# CH32M030C8U3-R0.net
KiCad netlist of a schematic drawn in Altium Designer
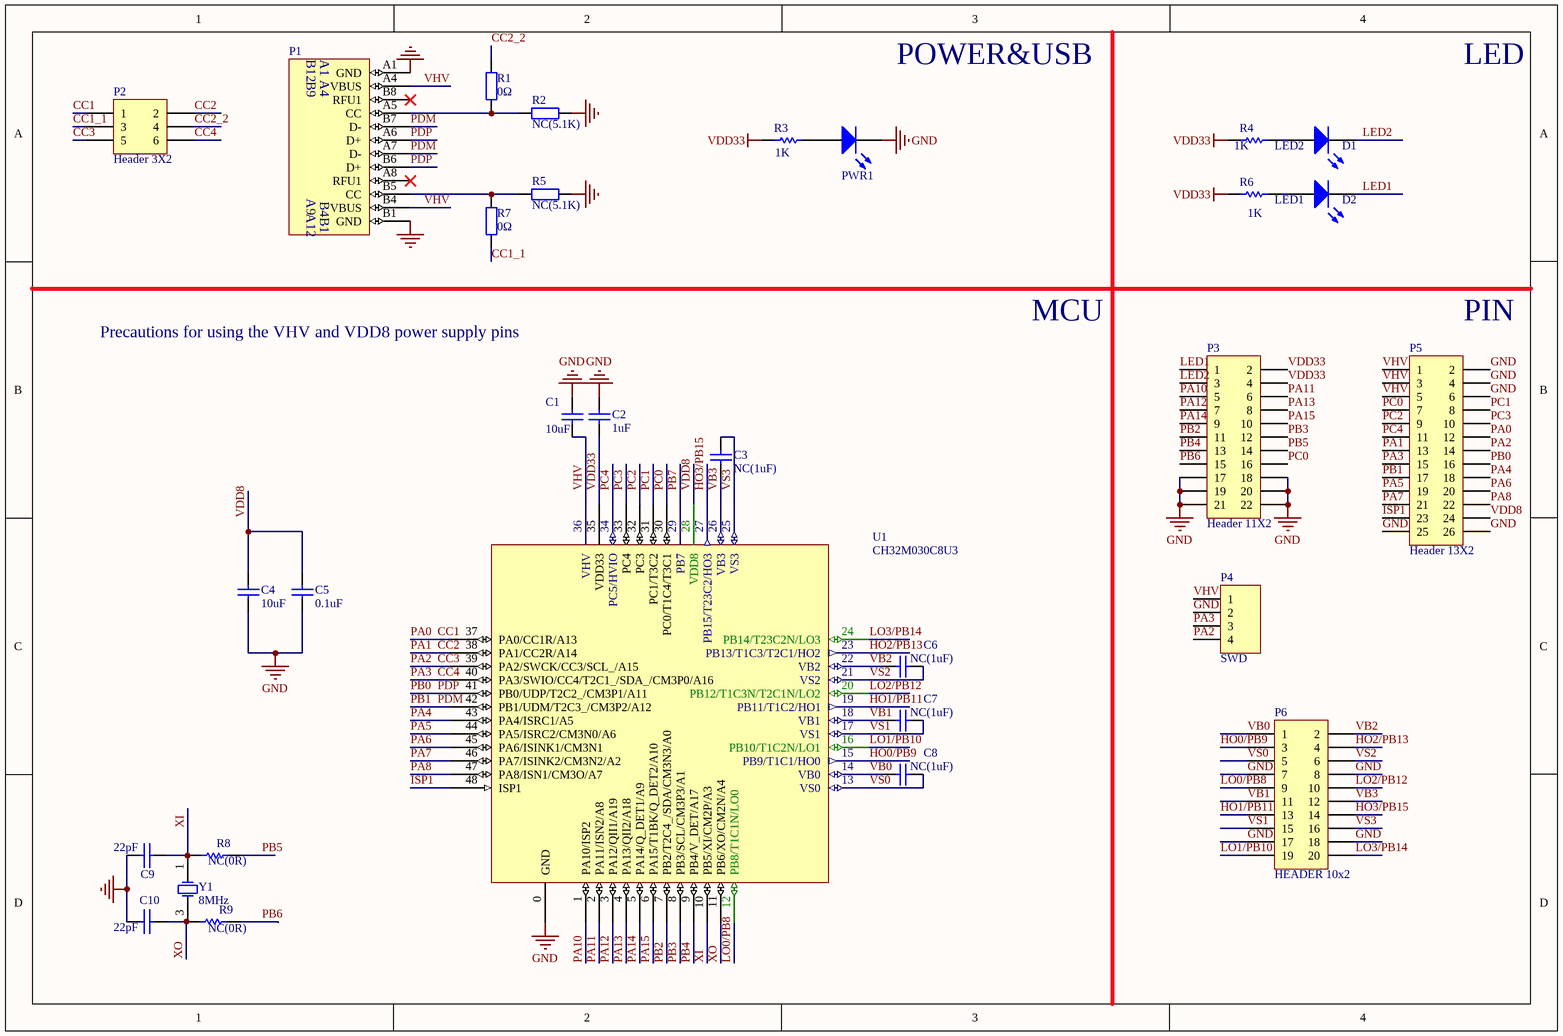
[diagram p0: CH32M030C8U3-R0.SchDoc]

(export (version "E")
  (design (tool "Eeschema 10.0.6"))
  (components
    (comp (ref "C1")
      (value "10uF")
      (footprint "0603_C")
      (description "Capacitor")
      (fields (field (name "PUBLISHER") "Altium Limited"))
      (libsource (lib "*") (part "Cap"))
    )
    (comp (ref "C2")
      (value "1uF")
      (footprint "0603_C")
      (description "Capacitor")
      (fields (field (name "PUBLISHER") "Altium Limited"))
      (libsource (lib "*") (part "Cap"))
    )
    (comp (ref "C3")
      (value "NC(1uF)")
      (footprint "0603_C")
      (description "Capacitor")
      (fields (field (name "PUBLISHER") "Altium Limited"))
      (libsource (lib "*") (part "Cap"))
    )
    (comp (ref "C4")
      (value "10uF")
      (footprint "0603_C")
      (description "Capacitor")
      (fields (field (name "PUBLISHER") "Altium Limited"))
      (libsource (lib "*") (part "Cap"))
    )
    (comp (ref "C5")
      (value "0.1uF")
      (footprint "0603_C")
      (description "Capacitor")
      (fields (field (name "PUBLISHER") "Altium Limited"))
      (libsource (lib "*") (part "Cap"))
    )
    (comp (ref "C6")
      (value "NC(1uF)")
      (footprint "0603_C")
      (description "Capacitor")
      (fields (field (name "PUBLISHER") "Altium Limited"))
      (libsource (lib "*") (part "Cap"))
    )
    (comp (ref "C7")
      (value "NC(1uF)")
      (footprint "0603_C")
      (description "Capacitor")
      (fields (field (name "PUBLISHER") "Altium Limited"))
      (libsource (lib "*") (part "Cap"))
    )
    (comp (ref "C8")
      (value "NC(1uF)")
      (footprint "0603_C")
      (description "Capacitor")
      (fields (field (name "PUBLISHER") "Altium Limited"))
      (libsource (lib "*") (part "Cap"))
    )
    (comp (ref "C9")
      (value "22pF")
      (footprint "0603_C")
      (description "Capacitor")
      (libsource (lib "*") (part "CAP"))
    )
    (comp (ref "C10")
      (value "22pF")
      (footprint "0603_C")
      (description "Capacitor")
      (libsource (lib "*") (part "CAP"))
    )
    (comp (ref "D1")
      (value "LED2")
      (footprint "0603+")
      (description "Typical INFRARED GaAs LED")
      (fields (field (name "PUBLISHER") "Altium Limited"))
      (libsource (lib "*") (part "LED0"))
    )
    (comp (ref "D2")
      (value "LED1")
      (footprint "0603+")
      (description "Typical INFRARED GaAs LED")
      (fields (field (name "PUBLISHER") "Altium Limited"))
      (libsource (lib "*") (part "LED0"))
    )
    (comp (ref "P1")
      (value "TYPE-C")
      (footprint "TYPE-C-Receptacle-2.0")
      (libsource (lib "*") (part "TYPE-C1"))
    )
    (comp (ref "P2")
      (value "Header 3X2")
      (footprint "IDC6-2.54mm")
      (description "Header, 3-Pin, Dual row")
      (fields (field (name "PUBLISHER") "Altium Limited"))
      (libsource (lib "Miscellaneous Connectors") (part "Header 3X2"))
    )
    (comp (ref "P3")
      (value "Header 11X2")
      (footprint "IDC22-2.54mm")
      (description "Header, 11-Pin, Dual row")
      (fields (field (name "PUBLISHER") "Altium Limited"))
      (libsource (lib "Miscellaneous Connectors") (part "Header 11X2"))
    )
    (comp (ref "P4")
      (value "SWD")
      (footprint "SIP4-2.54mm")
      (description "Header, 4-Pin")
      (libsource (lib "wch_sch_others") (part "HEADER 4"))
    )
    (comp (ref "P5")
      (value "Header 13X2")
      (footprint "IDC26-2.54mm")
      (description "Header, 13-Pin, Dual row")
      (fields (field (name "PUBLISHER") "Altium Limited"))
      (libsource (lib "Miscellaneous Connectors") (part "Header 13X2"))
    )
    (comp (ref "P6")
      (value "HEADER 10x2")
      (footprint "MYPCB:IDC20-2.54MM")
      (description "Header, 10-Pin, Dual row")
      (libsource (lib "wch_sch_others") (part "HEADER 10x2"))
    )
    (comp (ref "PWR1")
      (value "POWER  red")
      (footprint "0603+")
      (description "Typical INFRARED GaAs LED")
      (fields (field (name "PUBLISHER") "Altium Limited"))
      (libsource (lib "*") (part "LED0"))
    )
    (comp (ref "R1")
      (value "0Ω")
      (footprint "0603")
      (description "Resistor")
      (libsource (lib "Miscellaneous Devices") (part "Res2"))
    )
    (comp (ref "R2")
      (value "NC(5.1K)")
      (footprint "0603")
      (description "Resistor")
      (libsource (lib "") (part "Res2_1"))
    )
    (comp (ref "R3")
      (value "1K")
      (footprint "0603")
      (description "Semiconductor Resistor")
      (fields (field (name "PUBLISHER") "Altium Limited"))
      (libsource (lib "*") (part "Res Semi"))
    )
    (comp (ref "R4")
      (value "1K")
      (footprint "0603")
      (description "Semiconductor Resistor")
      (fields (field (name "PUBLISHER") "Altium Limited"))
      (libsource (lib "*") (part "Res Semi"))
    )
    (comp (ref "R5")
      (value "NC(5.1K)")
      (footprint "0603")
      (description "Resistor")
      (libsource (lib "") (part "Res2_1"))
    )
    (comp (ref "R6")
      (value "1K")
      (footprint "0603")
      (description "Semiconductor Resistor")
      (fields (field (name "PUBLISHER") "Altium Limited"))
      (libsource (lib "*") (part "Res Semi"))
    )
    (comp (ref "R7")
      (value "0Ω")
      (footprint "0603")
      (description "Resistor")
      (libsource (lib "Miscellaneous Devices") (part "Res2"))
    )
    (comp (ref "R8")
      (value "NC(0R)")
      (footprint "0603")
      (description "Semiconductor Resistor")
      (fields (field (name "PUBLISHER") "Altium Limited"))
      (libsource (lib "*") (part "Res Semi"))
    )
    (comp (ref "R9")
      (value "NC(0R)")
      (footprint "0603")
      (description "Semiconductor Resistor")
      (fields (field (name "PUBLISHER") "Altium Limited"))
      (libsource (lib "*") (part "Res Semi"))
    )
    (comp (ref "U1")
      (value "CH32M030C8U3")
      (footprint "QFN48_7X7")
      (description "RISC-V MCU, 72MHz, USB, Type-C/PD, OPA, CMP, 28V gate driver")
      (libsource (lib "CHXXX") (part "CH32M030C8U3"))
    )
    (comp (ref "Y1")
      (value "8MHz")
      (footprint "XT3225")
      (description "Crystal Oscillator")
      (fields (field (name "PUBLISHER") "Altium Limited"))
      (libsource (lib "*") (part "XTAL"))
    )
  )
  (nets
    (net (code "1") (name "/CC1") (class "Default")
      (node (ref "P2") (pin "1") (pinfunction "1_1") (pintype "passive"))
      (node (ref "P5") (pin "12") (pinfunction "12_12") (pintype "passive"))
      (node (ref "U1") (pin "37") (pinfunction "PA0/CC1R/A13_37") (pintype "bidirectional"))
    )
    (net (code "2") (name "/CC1_1") (class "Default")
      (node (ref "P2") (pin "3") (pinfunction "3_3") (pintype "passive"))
      (node (ref "R7") (pin "1") (pinfunction "1_1") (pintype "passive"))
    )
    (net (code "3") (name "/CC2") (class "Default")
      (node (ref "P2") (pin "2") (pinfunction "2_2") (pintype "passive"))
      (node (ref "P5") (pin "13") (pinfunction "13_13") (pintype "passive"))
      (node (ref "U1") (pin "38") (pinfunction "PA1/CC2R/A14_38") (pintype "bidirectional"))
    )
    (net (code "4") (name "/CC2_2") (class "Default")
      (node (ref "P2") (pin "4") (pinfunction "4_4") (pintype "passive"))
      (node (ref "R1") (pin "2") (pinfunction "2_2") (pintype "passive"))
    )
    (net (code "5") (name "/CC3") (class "Default")
      (node (ref "P2") (pin "5") (pinfunction "5_5") (pintype "passive"))
      (node (ref "P4") (pin "4") (pinfunction "4_4") (pintype "passive"))
      (node (ref "P5") (pin "14") (pinfunction "14_14") (pintype "passive"))
      (node (ref "U1") (pin "39") (pinfunction "PA2/SWCK/CC3/SCL_/A15_39") (pintype "bidirectional"))
    )
    (net (code "6") (name "/CC4") (class "Default")
      (node (ref "P2") (pin "6") (pinfunction "6_6") (pintype "passive"))
      (node (ref "P4") (pin "3") (pinfunction "3_3") (pintype "passive"))
      (node (ref "P5") (pin "15") (pinfunction "15_15") (pintype "passive"))
      (node (ref "U1") (pin "40") (pinfunction "PA3/SWIO/CC4/T2C1_/SDA_/CM3P0/A16_40") (pintype "bidirectional"))
    )
    (net (code "7") (name "/HO0{slash}PB9") (class "Default")
      (node (ref "P6") (pin "3") (pinfunction "3_3") (pintype "passive"))
      (node (ref "U1") (pin "15") (pinfunction "PB9/T1C1/HO0_15") (pintype "output"))
    )
    (net (code "8") (name "/HO1{slash}PB11") (class "Default")
      (node (ref "P6") (pin "13") (pinfunction "13_13") (pintype "passive"))
      (node (ref "U1") (pin "19") (pinfunction "PB11/T1C2/HO1_19") (pintype "output"))
    )
    (net (code "9") (name "/HO2{slash}PB13") (class "Default")
      (node (ref "P6") (pin "4") (pinfunction "4_4") (pintype "passive"))
      (node (ref "U1") (pin "23") (pinfunction "PB13/T1C3/T2C1/HO2_23") (pintype "output"))
    )
    (net (code "10") (name "/HO3{slash}PB15") (class "Default")
      (node (ref "P6") (pin "14") (pinfunction "14_14") (pintype "passive"))
      (node (ref "U1") (pin "27") (pinfunction "PB15/T23C2/HO3_27") (pintype "output"))
    )
    (net (code "11") (name "/ISP1") (class "Default")
      (node (ref "P5") (pin "23") (pinfunction "23_23") (pintype "passive"))
      (node (ref "U1") (pin "48") (pinfunction "ISP1_48") (pintype "input"))
    )
    (net (code "12") (name "/LED1") (class "Default")
      (node (ref "D2") (pin "2") (pinfunction "K_2") (pintype "passive"))
      (node (ref "P3") (pin "1") (pinfunction "1_1") (pintype "passive"))
    )
    (net (code "13") (name "/LED2") (class "Default")
      (node (ref "D1") (pin "2") (pinfunction "K_2") (pintype "passive"))
      (node (ref "P3") (pin "3") (pinfunction "3_3") (pintype "passive"))
    )
    (net (code "14") (name "/LO0{slash}PB8") (class "Default")
      (node (ref "P6") (pin "9") (pinfunction "9_9") (pintype "passive"))
      (node (ref "U1") (pin "12") (pinfunction "PB8/T1C1N/LO0_12") (pintype "bidirectional"))
    )
    (net (code "15") (name "/LO1{slash}PB10") (class "Default")
      (node (ref "P6") (pin "19") (pinfunction "19_19") (pintype "passive"))
      (node (ref "U1") (pin "16") (pinfunction "PB10/T1C2N/LO1_16") (pintype "bidirectional"))
    )
    (net (code "16") (name "/LO2{slash}PB12") (class "Default")
      (node (ref "P6") (pin "10") (pinfunction "10_10") (pintype "passive"))
      (node (ref "U1") (pin "20") (pinfunction "PB12/T1C3N/T2C1N/LO2_20") (pintype "bidirectional"))
    )
    (net (code "17") (name "/LO3{slash}PB14") (class "Default")
      (node (ref "P6") (pin "20") (pinfunction "20_20") (pintype "passive"))
      (node (ref "U1") (pin "24") (pinfunction "PB14/T23C2N/LO3_24") (pintype "bidirectional"))
    )
    (net (code "18") (name "/PA4") (class "Default")
      (node (ref "P5") (pin "18") (pinfunction "18_18") (pintype "passive"))
      (node (ref "U1") (pin "43") (pinfunction "PA4/ISRC1/A5_43") (pintype "bidirectional"))
    )
    (net (code "19") (name "/PA5") (class "Default")
      (node (ref "P5") (pin "19") (pinfunction "19_19") (pintype "passive"))
      (node (ref "U1") (pin "44") (pinfunction "PA5/ISRC2/CM3N0/A6_44") (pintype "bidirectional"))
    )
    (net (code "20") (name "/PA6") (class "Default")
      (node (ref "P5") (pin "20") (pinfunction "20_20") (pintype "passive"))
      (node (ref "U1") (pin "45") (pinfunction "PA6/ISINK1/CM3N1_45") (pintype "bidirectional"))
    )
    (net (code "21") (name "/PA7") (class "Default")
      (node (ref "P5") (pin "21") (pinfunction "21_21") (pintype "passive"))
      (node (ref "U1") (pin "46") (pinfunction "PA7/ISINK2/CM3N2/A2_46") (pintype "bidirectional"))
    )
    (net (code "22") (name "/PA8") (class "Default")
      (node (ref "P5") (pin "22") (pinfunction "22_22") (pintype "passive"))
      (node (ref "U1") (pin "47") (pinfunction "PA8/ISN1/CM3O/A7_47") (pintype "bidirectional"))
    )
    (net (code "23") (name "/PA10") (class "Default")
      (node (ref "P3") (pin "5") (pinfunction "5_5") (pintype "passive"))
      (node (ref "U1") (pin "1") (pinfunction "PA10/ISP2_1") (pintype "bidirectional"))
    )
    (net (code "24") (name "/PA11") (class "Default")
      (node (ref "P3") (pin "6") (pinfunction "6_6") (pintype "passive"))
      (node (ref "U1") (pin "2") (pinfunction "PA11/ISN2/A8_2") (pintype "bidirectional"))
    )
    (net (code "25") (name "/PA12") (class "Default")
      (node (ref "P3") (pin "7") (pinfunction "7_7") (pintype "passive"))
      (node (ref "U1") (pin "3") (pinfunction "PA12/QII1/A19_3") (pintype "bidirectional"))
    )
    (net (code "26") (name "/PA13") (class "Default")
      (node (ref "P3") (pin "8") (pinfunction "8_8") (pintype "passive"))
      (node (ref "U1") (pin "4") (pinfunction "PA13/QII2/A18_4") (pintype "bidirectional"))
    )
    (net (code "27") (name "/PA14") (class "Default")
      (node (ref "P3") (pin "9") (pinfunction "9_9") (pintype "passive"))
      (node (ref "U1") (pin "5") (pinfunction "PA14/Q_DET1/A9_5") (pintype "bidirectional"))
    )
    (net (code "28") (name "/PA15") (class "Default")
      (node (ref "P3") (pin "10") (pinfunction "10_10") (pintype "passive"))
      (node (ref "U1") (pin "6") (pinfunction "PA15/T1BK/Q_DET2/A10_6") (pintype "bidirectional"))
    )
    (net (code "29") (name "/PB0") (class "Default")
      (node (ref "P1") (pin "A6") (pinfunction "D+_A6") (pintype "bidirectional"))
      (node (ref "P1") (pin "B6") (pinfunction "D+_B6") (pintype "bidirectional"))
      (node (ref "P5") (pin "16") (pinfunction "16_16") (pintype "passive"))
      (node (ref "U1") (pin "41") (pinfunction "PB0/UDP/T2C2_/CM3P1/A11_41") (pintype "bidirectional"))
    )
    (net (code "30") (name "/PB1") (class "Default")
      (node (ref "P1") (pin "A7") (pinfunction "D-_A7") (pintype "bidirectional"))
      (node (ref "P1") (pin "B7") (pinfunction "D-_B7") (pintype "bidirectional"))
      (node (ref "P5") (pin "17") (pinfunction "17_17") (pintype "passive"))
      (node (ref "U1") (pin "42") (pinfunction "PB1/UDM/T2C3_/CM3P2/A12_42") (pintype "bidirectional"))
    )
    (net (code "31") (name "/PB2") (class "Default")
      (node (ref "P3") (pin "11") (pinfunction "11_11") (pintype "passive"))
      (node (ref "U1") (pin "7") (pinfunction "PB2/T2C4_/SDA/CM3N3/A0_7") (pintype "bidirectional"))
    )
    (net (code "32") (name "/PB3") (class "Default")
      (node (ref "P3") (pin "12") (pinfunction "12_12") (pintype "passive"))
      (node (ref "U1") (pin "8") (pinfunction "PB3/SCL/CM3P3/A1_8") (pintype "bidirectional"))
    )
    (net (code "33") (name "/PB4") (class "Default")
      (node (ref "P3") (pin "13") (pinfunction "13_13") (pintype "passive"))
      (node (ref "U1") (pin "9") (pinfunction "PB4/V_DET/A17_9") (pintype "bidirectional"))
    )
    (net (code "34") (name "/PB5") (class "Default")
      (node (ref "P3") (pin "14") (pinfunction "14_14") (pintype "passive"))
      (node (ref "R8") (pin "2") (pinfunction "2_2") (pintype "passive"))
    )
    (net (code "35") (name "/PB6") (class "Default")
      (node (ref "P3") (pin "15") (pinfunction "15_15") (pintype "passive"))
      (node (ref "R9") (pin "2") (pinfunction "2_2") (pintype "passive"))
    )
    (net (code "36") (name "/PB7") (class "Default")
      (node (ref "U1") (pin "29") (pinfunction "PB7_29") (pintype "open_collector"))
    )
    (net (code "37") (name "/PC0") (class "Default")
      (node (ref "P3") (pin "16") (pinfunction "16_16") (pintype "passive"))
      (node (ref "P5") (pin "7") (pinfunction "7_7") (pintype "passive"))
      (node (ref "U1") (pin "30") (pinfunction "PC0/T1C4/T3C1_30") (pintype "bidirectional"))
    )
    (net (code "38") (name "/PC1") (class "Default")
      (node (ref "P5") (pin "8") (pinfunction "8_8") (pintype "passive"))
      (node (ref "U1") (pin "31") (pinfunction "PC1/T3C2_31") (pintype "bidirectional"))
    )
    (net (code "39") (name "/PC2") (class "Default")
      (node (ref "P5") (pin "9") (pinfunction "9_9") (pintype "passive"))
      (node (ref "U1") (pin "32") (pinfunction "PC3_32") (pintype "bidirectional"))
    )
    (net (code "40") (name "/PC3") (class "Default")
      (node (ref "P5") (pin "10") (pinfunction "10_10") (pintype "passive"))
      (node (ref "U1") (pin "33") (pinfunction "PC4_33") (pintype "bidirectional"))
    )
    (net (code "41") (name "/PC4") (class "Default")
      (node (ref "P5") (pin "11") (pinfunction "11_11") (pintype "passive"))
      (node (ref "U1") (pin "34") (pinfunction "PC5/HVIO_34") (pintype "bidirectional"))
    )
    (net (code "42") (name "/VB0") (class "Default")
      (node (ref "C8") (pin "2") (pinfunction "2_2") (pintype "passive"))
      (node (ref "P6") (pin "1") (pinfunction "1_1") (pintype "passive"))
      (node (ref "U1") (pin "14") (pinfunction "VB0_14") (pintype "bidirectional"))
    )
    (net (code "43") (name "/VB1") (class "Default")
      (node (ref "C7") (pin "2") (pinfunction "2_2") (pintype "passive"))
      (node (ref "P6") (pin "11") (pinfunction "11_11") (pintype "passive"))
      (node (ref "U1") (pin "18") (pinfunction "VB1_18") (pintype "bidirectional"))
    )
    (net (code "44") (name "/VB2") (class "Default")
      (node (ref "C6") (pin "2") (pinfunction "2_2") (pintype "passive"))
      (node (ref "P6") (pin "2") (pinfunction "2_2") (pintype "passive"))
      (node (ref "U1") (pin "22") (pinfunction "VB2_22") (pintype "bidirectional"))
    )
    (net (code "45") (name "/VB3") (class "Default")
      (node (ref "C3") (pin "2") (pinfunction "2_2") (pintype "passive"))
      (node (ref "P6") (pin "12") (pinfunction "12_12") (pintype "passive"))
      (node (ref "U1") (pin "26") (pinfunction "VB3_26") (pintype "bidirectional"))
    )
    (net (code "46") (name "/VDD8") (class "Default")
      (node (ref "C4") (pin "2") (pinfunction "2_2") (pintype "passive"))
      (node (ref "C5") (pin "2") (pinfunction "2_2") (pintype "passive"))
      (node (ref "P5") (pin "24") (pinfunction "24_24") (pintype "passive"))
      (node (ref "U1") (pin "28") (pinfunction "VDD8_28") (pintype "power_in"))
    )
    (net (code "47") (name "/VHV") (class "Default")
      (node (ref "C1") (pin "1") (pinfunction "1_1") (pintype "passive"))
      (node (ref "P1") (pin "A4") (pinfunction "VBUS_A4") (pintype "bidirectional"))
      (node (ref "P1") (pin "B4") (pinfunction "VBUS_B4") (pintype "bidirectional"))
      (node (ref "P4") (pin "1") (pinfunction "1_1") (pintype "passive"))
      (node (ref "P5") (pin "1") (pinfunction "1_1") (pintype "passive"))
      (node (ref "P5") (pin "3") (pinfunction "3_3") (pintype "passive"))
      (node (ref "P5") (pin "5") (pinfunction "5_5") (pintype "passive"))
      (node (ref "U1") (pin "36") (pinfunction "VHV_36") (pintype "power_in"))
    )
    (net (code "48") (name "/VS0") (class "Default")
      (node (ref "C8") (pin "1") (pinfunction "1_1") (pintype "passive"))
      (node (ref "P6") (pin "5") (pinfunction "5_5") (pintype "passive"))
      (node (ref "U1") (pin "13") (pinfunction "VS0_13") (pintype "bidirectional"))
    )
    (net (code "49") (name "/VS1") (class "Default")
      (node (ref "C7") (pin "1") (pinfunction "1_1") (pintype "passive"))
      (node (ref "P6") (pin "15") (pinfunction "15_15") (pintype "passive"))
      (node (ref "U1") (pin "17") (pinfunction "VS1_17") (pintype "bidirectional"))
    )
    (net (code "50") (name "/VS2") (class "Default")
      (node (ref "C6") (pin "1") (pinfunction "1_1") (pintype "passive"))
      (node (ref "P6") (pin "6") (pinfunction "6_6") (pintype "passive"))
      (node (ref "U1") (pin "21") (pinfunction "VS2_21") (pintype "bidirectional"))
    )
    (net (code "51") (name "/VS3") (class "Default")
      (node (ref "C3") (pin "1") (pinfunction "1_1") (pintype "passive"))
      (node (ref "P6") (pin "16") (pinfunction "16_16") (pintype "passive"))
      (node (ref "U1") (pin "25") (pinfunction "VS3_25") (pintype "bidirectional"))
    )
    (net (code "52") (name "/XI") (class "Default")
      (node (ref "C9") (pin "2") (pinfunction "2_2") (pintype "passive"))
      (node (ref "R8") (pin "1") (pinfunction "1_1") (pintype "passive"))
      (node (ref "U1") (pin "10") (pinfunction "PB5/XI/CM2P/A3_10") (pintype "bidirectional"))
      (node (ref "Y1") (pin "1") (pinfunction "OSC1_1") (pintype "passive"))
    )
    (net (code "53") (name "/XO") (class "Default")
      (node (ref "C10") (pin "2") (pinfunction "2_2") (pintype "passive"))
      (node (ref "R9") (pin "1") (pinfunction "1_1") (pintype "passive"))
      (node (ref "U1") (pin "11") (pinfunction "PB6/XO/CM2N/A4_11") (pintype "bidirectional"))
    )
    (net (code "54") (name "GND") (class "Default")
      (node (ref "C1") (pin "2") (pinfunction "2_2") (pintype "passive"))
      (node (ref "C10") (pin "1") (pinfunction "1_1") (pintype "passive"))
      (node (ref "C2") (pin "2") (pinfunction "2_2") (pintype "passive"))
      (node (ref "C4") (pin "1") (pinfunction "1_1") (pintype "passive"))
      (node (ref "C5") (pin "1") (pinfunction "1_1") (pintype "passive"))
      (node (ref "C9") (pin "1") (pinfunction "1_1") (pintype "passive"))
      (node (ref "P1") (pin "A1") (pinfunction "GND_A1") (pintype "bidirectional"))
      (node (ref "P1") (pin "B1") (pinfunction "GND_B1") (pintype "bidirectional"))
      (node (ref "P3") (pin "17") (pinfunction "17_17") (pintype "passive"))
      (node (ref "P3") (pin "18") (pinfunction "18_18") (pintype "passive"))
      (node (ref "P3") (pin "19") (pinfunction "19_19") (pintype "passive"))
      (node (ref "P3") (pin "20") (pinfunction "20_20") (pintype "passive"))
      (node (ref "P3") (pin "21") (pinfunction "21_21") (pintype "passive"))
      (node (ref "P3") (pin "22") (pinfunction "22_22") (pintype "passive"))
      (node (ref "P4") (pin "2") (pinfunction "2_2") (pintype "passive"))
      (node (ref "P5") (pin "2") (pinfunction "2_2") (pintype "passive"))
      (node (ref "P5") (pin "25") (pinfunction "25_25") (pintype "passive"))
      (node (ref "P5") (pin "26") (pinfunction "26_26") (pintype "passive"))
      (node (ref "P5") (pin "4") (pinfunction "4_4") (pintype "passive"))
      (node (ref "P5") (pin "6") (pinfunction "6_6") (pintype "passive"))
      (node (ref "P6") (pin "17") (pinfunction "17_17") (pintype "passive"))
      (node (ref "P6") (pin "18") (pinfunction "18_18") (pintype "passive"))
      (node (ref "P6") (pin "7") (pinfunction "7_7") (pintype "passive"))
      (node (ref "P6") (pin "8") (pinfunction "8_8") (pintype "passive"))
      (node (ref "PWR1") (pin "2") (pinfunction "K_2") (pintype "passive"))
      (node (ref "R2") (pin "2") (pinfunction "2_2") (pintype "passive"))
      (node (ref "R5") (pin "2") (pinfunction "2_2") (pintype "passive"))
      (node (ref "U1") (pin "0") (pinfunction "GND_0") (pintype "power_in"))
    )
    (net (code "55") (name "Net-(D1-A)") (class "Default")
      (node (ref "D1") (pin "1") (pinfunction "A_1") (pintype "passive"))
      (node (ref "R4") (pin "2") (pinfunction "2_2") (pintype "passive"))
    )
    (net (code "56") (name "Net-(D2-A)") (class "Default")
      (node (ref "D2") (pin "1") (pinfunction "A_1") (pintype "passive"))
      (node (ref "R6") (pin "2") (pinfunction "2_2") (pintype "passive"))
    )
    (net (code "57") (name "Net-(P1-CC-PadA5)") (class "Default")
      (node (ref "P1") (pin "A5") (pinfunction "CC_A5") (pintype "bidirectional"))
      (node (ref "R1") (pin "1") (pinfunction "1_1") (pintype "passive"))
      (node (ref "R2") (pin "1") (pinfunction "1_1") (pintype "passive"))
    )
    (net (code "58") (name "Net-(P1-CC-PadB5)") (class "Default")
      (node (ref "P1") (pin "B5") (pinfunction "CC_B5") (pintype "bidirectional"))
      (node (ref "R5") (pin "1") (pinfunction "1_1") (pintype "passive"))
      (node (ref "R7") (pin "2") (pinfunction "2_2") (pintype "passive"))
    )
    (net (code "59") (name "Net-(PWR1-A)") (class "Default")
      (node (ref "PWR1") (pin "1") (pinfunction "A_1") (pintype "passive"))
      (node (ref "R3") (pin "1") (pinfunction "1_1") (pintype "passive"))
    )
    (net (code "60") (name "VDD33") (class "Default")
      (node (ref "C2") (pin "1") (pinfunction "1_1") (pintype "passive"))
      (node (ref "P3") (pin "2") (pinfunction "2_2") (pintype "passive"))
      (node (ref "P3") (pin "4") (pinfunction "4_4") (pintype "passive"))
      (node (ref "R3") (pin "2") (pinfunction "2_2") (pintype "passive"))
      (node (ref "R4") (pin "1") (pinfunction "1_1") (pintype "passive"))
      (node (ref "R6") (pin "1") (pinfunction "1_1") (pintype "passive"))
      (node (ref "U1") (pin "35") (pinfunction "VDD33_35") (pintype "power_in"))
    )
    (net (code "61") (name "unconnected-(P1-RFU1-PadA8)") (class "Default")
      (node (ref "P1") (pin "A8") (pinfunction "RFU1_A8") (pintype "bidirectional+no_connect"))
    )
    (net (code "62") (name "unconnected-(P1-RFU1-PadB8)") (class "Default")
      (node (ref "P1") (pin "B8") (pinfunction "RFU1_B8") (pintype "bidirectional+no_connect"))
    )
    (net (code "63") (name "unconnected-(Y1-OSC2-Pad3)") (class "Default")
      (node (ref "Y1") (pin "3") (pinfunction "OSC2_3") (pintype "passive"))
    )
  )
)
